# RS485_Xbus_Mini.net
KiCad netlist of a schematic drawn in Altium Designer
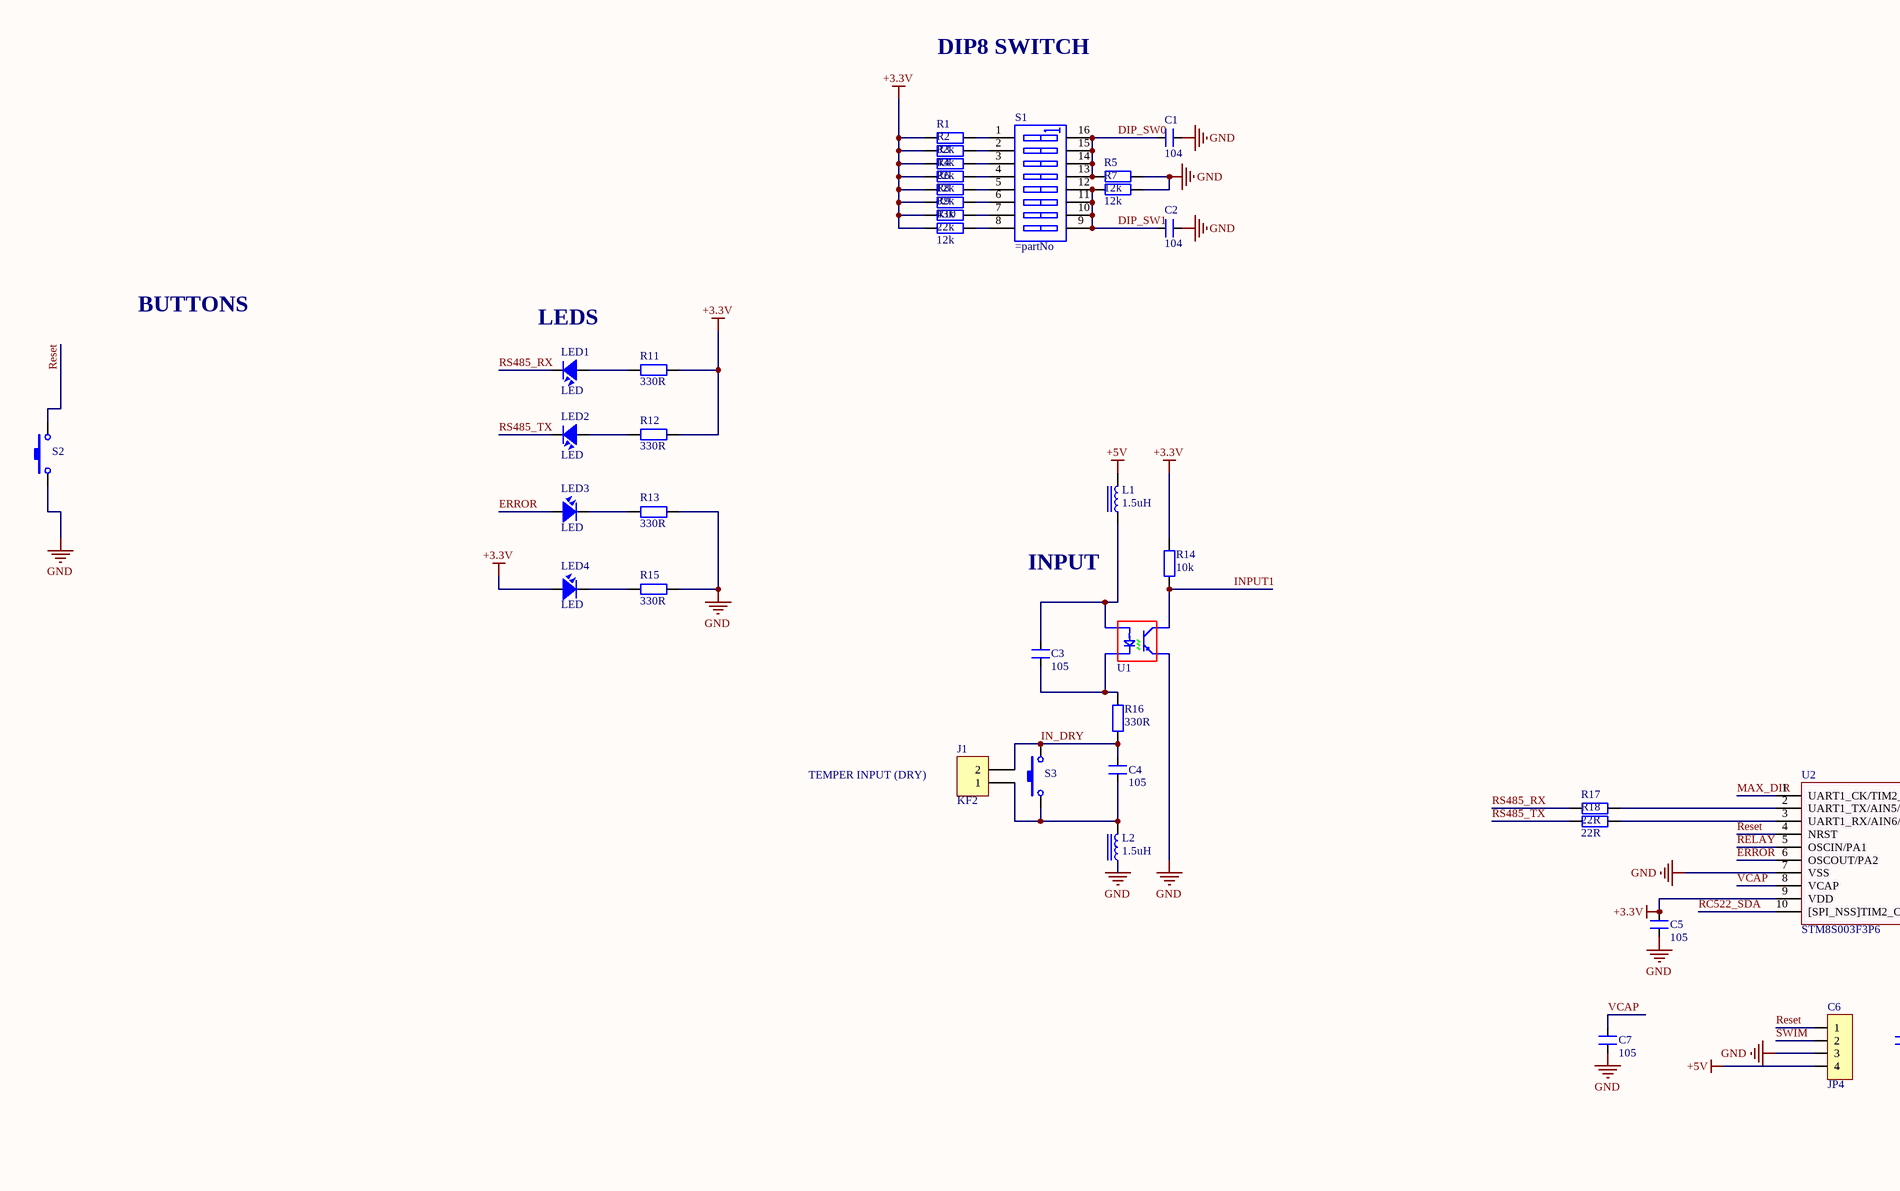
[diagram p0: RS485_Xbus_Mini.SchDoc, left]
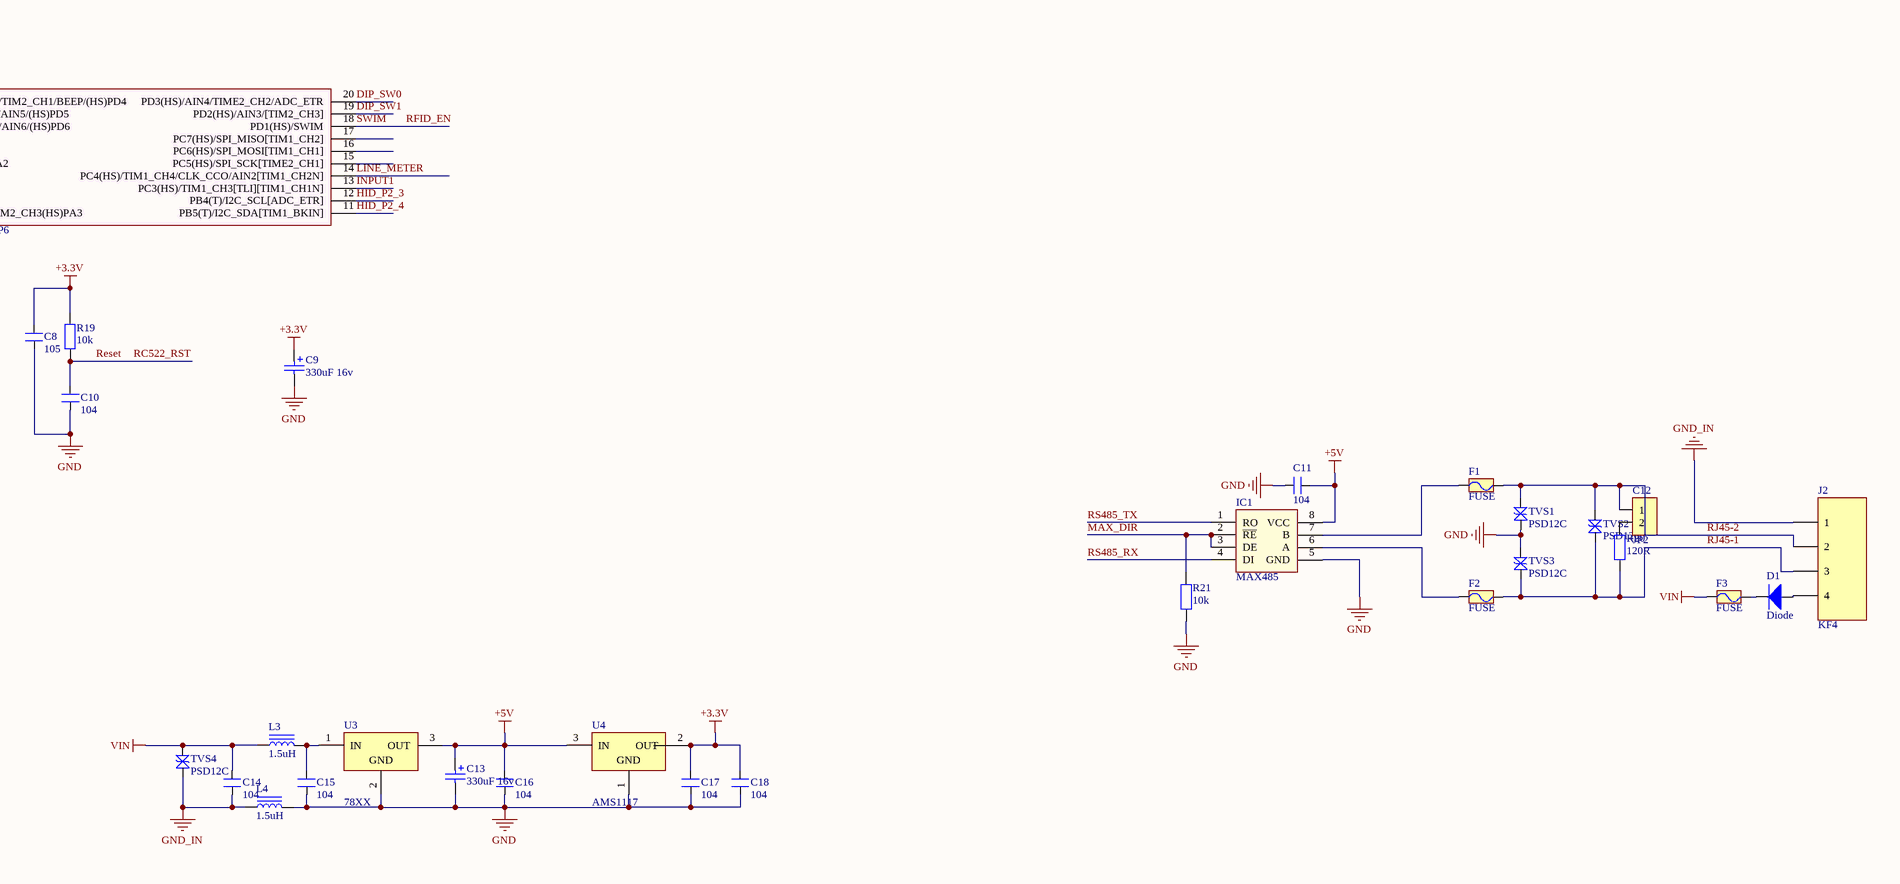
[diagram p1: RS485_Xbus_Mini.SchDoc, right]

(export (version "E")
  (design (tool "Eeschema 10.0.6"))
  (components
    (comp (ref "C1")
      (value "104")
      (footprint "SM-0805")
      (description "Cap SMD")
      (libsource (lib "OBIT_TESLA") (part "CM"))
    )
    (comp (ref "C2")
      (value "104")
      (footprint "SM-0805")
      (description "Cap SMD")
      (libsource (lib "OBIT_TESLA") (part "CM"))
    )
    (comp (ref "C3")
      (value "105")
      (footprint "SM-0805")
      (description "Cap SMD")
      (libsource (lib "OBIT_TESLA") (part "CM"))
    )
    (comp (ref "C4")
      (value "105")
      (footprint "SM-0805")
      (description "Cap SMD")
      (libsource (lib "OBIT_TESLA") (part "CM"))
    )
    (comp (ref "C5")
      (value "105")
      (footprint "SM-0805")
      (description "Cap SMD")
      (libsource (lib "OBIT_TESLA") (part "CM"))
    )
    (comp (ref "C6")
      (value "JP4")
      (footprint "JP4-C1T")
      (description "WR-PHD 2.54 mm Angled Socket Header")
      (fields
        (field (name "MANUFACTURER") "Würth Elektronik eiSos GmbH")
        (field (name "PARTNO") "613004143121")
        (field (name "CREATED BY") "Karrer Zheng")
      )
      (libsource (lib "OBIT_TESLA") (part "JP4"))
    )
    (comp (ref "C7")
      (value "105")
      (footprint "SM-0805")
      (description "Cap SMD")
      (libsource (lib "OBIT_TESLA") (part "CM"))
    )
    (comp (ref "C8")
      (value "105")
      (footprint "SM-0805")
      (description "Cap SMD")
      (libsource (lib "OBIT_TESLA") (part "CM"))
    )
    (comp (ref "C9")
      (value "330uF 16v")
      (footprint "WCAP-AS5H_8x10.5")
      (description "https://banlinhkien.vn/goods-2220-tu-nhom-330uf-16v-8x10mm.html")
      (fields (field (name "PARTNUMBER") "865230153006") (field (name "PUBLISHER") "Wurth Elektronik"))
      (libsource (lib "Library") (part "CAP/330uF/6.3V/865230153006"))
    )
    (comp (ref "C10")
      (value "104")
      (footprint "SM-0805")
      (description "Cap SMD")
      (libsource (lib "OBIT_TESLA") (part "CM"))
    )
    (comp (ref "C11")
      (value "104")
      (footprint "SM-0805")
      (description "Cap SMD")
      (libsource (lib "OBIT_TESLA") (part "CM"))
    )
    (comp (ref "C12")
      (value "JP2")
      (footprint "JP2-D1T")
      (description "WR-PHD 2.54 mm Angled Socket Header")
      (fields
        (field (name "MANUFACTURER") "Würth Elektronik eiSos GmbH")
        (field (name "PARTNO") "613002143121")
        (field (name "CREATED BY") "Karrer Zheng")
      )
      (libsource (lib "OBIT_TESLA") (part "JP2"))
    )
    (comp (ref "C13")
      (value "330uF 16v")
      (footprint "WCAP-AS5H_8x10.5")
      (description "https://banlinhkien.vn/goods-2220-tu-nhom-330uf-16v-8x10mm.html")
      (fields (field (name "PARTNUMBER") "865230153006") (field (name "PUBLISHER") "Wurth Elektronik"))
      (libsource (lib "Library") (part "CAP/330uF/6.3V/865230153006"))
    )
    (comp (ref "C14")
      (value "104")
      (footprint "SM-0805")
      (description "Cap SMD")
      (libsource (lib "OBIT_TESLA") (part "CM"))
    )
    (comp (ref "C15")
      (value "104")
      (footprint "SM-0805")
      (description "Cap SMD")
      (libsource (lib "OBIT_TESLA") (part "CM"))
    )
    (comp (ref "C16")
      (value "104")
      (footprint "SM-0805")
      (description "Cap SMD")
      (libsource (lib "OBIT_TESLA") (part "CM"))
    )
    (comp (ref "C17")
      (value "104")
      (footprint "SM-0805")
      (description "Cap SMD")
      (libsource (lib "OBIT_TESLA") (part "CM"))
    )
    (comp (ref "C18")
      (value "104")
      (footprint "SM-0805")
      (description "Cap SMD")
      (libsource (lib "OBIT_TESLA") (part "CM"))
    )
    (comp (ref "D1") (value "Diode") (footprint "DIO-SMD-106") (libsource (lib "OBIT_TESLA") (part "Diode")))
    (comp (ref "F1") (value "FUSE") (footprint "RES-SMD-1812") (libsource (lib "OBIT_TESLA") (part "FUSE")))
    (comp (ref "F2") (value "FUSE") (footprint "RES-SMD-1812") (libsource (lib "OBIT_TESLA") (part "FUSE")))
    (comp (ref "F3") (value "FUSE") (footprint "RES-SMD-1812") (libsource (lib "OBIT_TESLA") (part "FUSE")))
    (comp (ref "IC1")
      (value "MAX485")
      (footprint "SO-8")
      (description "RS232 - RS485 (Same sn75176)")
      (libsource (lib "syhaunguyen") (part "MAX485"))
    )
    (comp (ref "J1")
      (value "KF2")
      (footprint "KF2-5.08")
      (fields
        (field (name "MANUFACTURER") "Würth Elektronik eiSos GmbH")
        (field (name "PARTNO") "691103110002")
        (field (name "CREATED BY") "Karrer Zheng")
      )
      (libsource (lib "OBIT_TESLA") (part "KF2"))
    )
    (comp (ref "J2")
      (value "KF4")
      (footprint "KF4-5.08")
      (fields
        (field (name "MANUFACTURER") "Würth Elektronik eiSos GmbH")
        (field (name "PARTNO") "691133710004")
        (field (name "CREATED BY") "Baojun Chen")
      )
      (libsource (lib "OBIT_TESLA") (part "KF4"))
    )
    (comp (ref "L1")
      (value "1.5uH")
      (footprint "FER 0805/2012")
      (description "SMT Inductor")
      (libsource (lib "OBIT_TESLA") (part "Inductor"))
    )
    (comp (ref "L2")
      (value "1.5uH")
      (footprint "FER 0805/2012")
      (description "SMT Inductor")
      (libsource (lib "OBIT_TESLA") (part "Inductor"))
    )
    (comp (ref "L3")
      (value "1.5uH")
      (footprint "FER 0805/2012")
      (description "SMT Inductor")
      (libsource (lib "OBIT_TESLA") (part "Inductor"))
    )
    (comp (ref "L4")
      (value "1.5uH")
      (footprint "FER 0805/2012")
      (description "SMT Inductor")
      (libsource (lib "OBIT_TESLA") (part "Inductor"))
    )
    (comp (ref "LED1")
      (value "LED")
      (footprint "SM-LED-0805-Green")
      (libsource (lib "OBIT_TESLA") (part "LED"))
    )
    (comp (ref "LED2")
      (value "LED")
      (footprint "SM-LED-0805-Blue")
      (libsource (lib "OBIT_TESLA") (part "LED"))
    )
    (comp (ref "LED3")
      (value "LED")
      (footprint "SM-LED-0805-Red")
      (libsource (lib "OBIT_TESLA") (part "LED"))
    )
    (comp (ref "LED4")
      (value "LED")
      (footprint "SM-LED-0805-Red")
      (libsource (lib "OBIT_TESLA") (part "LED"))
    )
    (comp (ref "R1")
      (value "82k")
      (footprint "RES-SMD-0805")
      (description "Resistor R1/4W")
      (libsource (lib "OBIT_TESLA") (part "R"))
    )
    (comp (ref "R2")
      (value "43k")
      (footprint "RES-SMD-0805")
      (description "Resistor R1/4W")
      (libsource (lib "OBIT_TESLA") (part "R"))
    )
    (comp (ref "R3")
      (value "22k")
      (footprint "RES-SMD-0805")
      (description "Resistor R1/4W")
      (libsource (lib "OBIT_TESLA") (part "R"))
    )
    (comp (ref "R4")
      (value "12k")
      (footprint "RES-SMD-0805")
      (description "Resistor R1/4W")
      (libsource (lib "OBIT_TESLA") (part "R"))
    )
    (comp (ref "R5")
      (value "12k")
      (footprint "RES-SMD-0805")
      (description "Resistor R1/4W")
      (libsource (lib "OBIT_TESLA") (part "R"))
    )
    (comp (ref "R6")
      (value "82k")
      (footprint "RES-SMD-0805")
      (description "Resistor R1/4W")
      (libsource (lib "OBIT_TESLA") (part "R"))
    )
    (comp (ref "R7")
      (value "12k")
      (footprint "RES-SMD-0805")
      (description "Resistor R1/4W")
      (libsource (lib "OBIT_TESLA") (part "R"))
    )
    (comp (ref "R8")
      (value "43k")
      (footprint "RES-SMD-0805")
      (description "Resistor R1/4W")
      (libsource (lib "OBIT_TESLA") (part "R"))
    )
    (comp (ref "R9")
      (value "22k")
      (footprint "RES-SMD-0805")
      (description "Resistor R1/4W")
      (libsource (lib "OBIT_TESLA") (part "R"))
    )
    (comp (ref "R10")
      (value "12k")
      (footprint "RES-SMD-0805")
      (description "Resistor R1/4W")
      (libsource (lib "OBIT_TESLA") (part "R"))
    )
    (comp (ref "R11")
      (value "330R")
      (footprint "RES-SMD-0805")
      (description "Resistor R1/4W")
      (libsource (lib "OBIT_TESLA") (part "R"))
    )
    (comp (ref "R12")
      (value "330R")
      (footprint "RES-SMD-0805")
      (description "Resistor R1/4W")
      (libsource (lib "OBIT_TESLA") (part "R"))
    )
    (comp (ref "R13")
      (value "330R")
      (footprint "RES-SMD-0805")
      (description "Resistor R1/4W")
      (libsource (lib "OBIT_TESLA") (part "R"))
    )
    (comp (ref "R14")
      (value "10k")
      (footprint "RES-SMD-0805")
      (description "Resistor R1/4W")
      (libsource (lib "OBIT_TESLA") (part "R"))
    )
    (comp (ref "R15")
      (value "330R")
      (footprint "RES-SMD-0805")
      (description "Resistor R1/4W")
      (libsource (lib "OBIT_TESLA") (part "R"))
    )
    (comp (ref "R16")
      (value "330R")
      (footprint "RES-SMD-0805")
      (description "Resistor R1/4W")
      (libsource (lib "OBIT_TESLA") (part "R"))
    )
    (comp (ref "R17")
      (value "22R")
      (footprint "RES-SMD-0805")
      (description "Resistor R1/4W")
      (libsource (lib "OBIT_TESLA") (part "R"))
    )
    (comp (ref "R18")
      (value "22R")
      (footprint "RES-SMD-0805")
      (description "Resistor R1/4W")
      (libsource (lib "OBIT_TESLA") (part "R"))
    )
    (comp (ref "R19")
      (value "10k")
      (footprint "RES-SMD-0805")
      (description "Resistor R1/4W")
      (libsource (lib "OBIT_TESLA") (part "R"))
    )
    (comp (ref "R20")
      (value "120R")
      (footprint "RES-SMD-0805")
      (description "Resistor R1/4W")
      (libsource (lib "OBIT_TESLA") (part "R"))
    )
    (comp (ref "R21")
      (value "10k")
      (footprint "RES-SMD-0805")
      (description "Resistor R1/4W")
      (libsource (lib "OBIT_TESLA") (part "R"))
    )
    (comp (ref "S1")
      (value "~")
      (footprint "SW-DIP8")
      (description "WS-DITV 2.54 mm small compact THT flat actuator with top tape")
      (fields
        (field (name "MANUFACTURER") "Wurth Elektronik")
        (field (name "PART NO.") "418127160908")
        (field (name "CREATED BY") "Baojun Chen")
      )
      (libsource (lib "OBIT_TESLA") (part "SWDIP8"))
    )
    (comp (ref "S2")
      (value "SW")
      (footprint "BUTTON-SMD 2PIN")
      (description "Switch-Button")
      (fields (field (name "PUBLISHER") "Altium Limited"))
      (libsource (lib "OBIT_TESLA") (part "SW-Button"))
    )
    (comp (ref "S3")
      (value "SW")
      (footprint "BUTTON-SMD 2PIN")
      (description "Switch-Button")
      (fields (field (name "PUBLISHER") "Altium Limited"))
      (libsource (lib "OBIT_TESLA") (part "SW-Button"))
    )
    (comp (ref "TVS1")
      (value "PSD12C")
      (footprint "DIO-SMD-123")
      (libsource (lib "OBIT_TESLA") (part "Diode TVS"))
    )
    (comp (ref "TVS2")
      (value "PSD12C")
      (footprint "DIO-SMD-123")
      (libsource (lib "OBIT_TESLA") (part "Diode TVS"))
    )
    (comp (ref "TVS3")
      (value "PSD12C")
      (footprint "DIO-SMD-123")
      (libsource (lib "OBIT_TESLA") (part "Diode TVS"))
    )
    (comp (ref "TVS4")
      (value "PSD12C")
      (footprint "DIO-SMD-B")
      (libsource (lib "OBIT_TESLA") (part "Diode TVS"))
    )
    (comp (ref "U1")
      (value "EL3H7 Opto")
      (footprint "SSOP4")
      (libsource (lib "OBIT_TESLA") (part "EL3H7 Opto"))
    )
    (comp (ref "U2")
      (value "STM8S003F3P6")
      (footprint "TSOP20")
      (description "MCU 8BIT 8KB FLASH TSSOP20")
      (libsource (lib "MCU") (part "STM8S003F3P6"))
    )
    (comp (ref "U3") (value "78XX") (footprint "SOT-89-321") (libsource (lib "OBIT_TESLA") (part "LM78XX")))
    (comp (ref "U4") (value "AMS1117") (footprint "SOT223") (libsource (lib "OBIT_TESLA") (part "AMS117")))
  )
  (nets
    (net (code "1") (name "+3.3V") (class "Default")
      (node (ref "C17") (pin "2") (pinfunction "2_2") (pintype "passive"))
      (node (ref "C18") (pin "2") (pinfunction "2_2") (pintype "passive"))
      (node (ref "C5") (pin "2") (pinfunction "2_2") (pintype "passive"))
      (node (ref "C8") (pin "2") (pinfunction "2_2") (pintype "passive"))
      (node (ref "C9") (pin "1") (pinfunction "P_1") (pintype "passive"))
      (node (ref "LED4") (pin "1") (pinfunction "1_1") (pintype "passive"))
      (node (ref "R1") (pin "2") (pinfunction "2_2") (pintype "passive"))
      (node (ref "R10") (pin "2") (pinfunction "2_2") (pintype "passive"))
      (node (ref "R11") (pin "1") (pinfunction "1_1") (pintype "passive"))
      (node (ref "R12") (pin "1") (pinfunction "1_1") (pintype "passive"))
      (node (ref "R14") (pin "2") (pinfunction "2_2") (pintype "passive"))
      (node (ref "R19") (pin "2") (pinfunction "2_2") (pintype "passive"))
      (node (ref "R2") (pin "2") (pinfunction "2_2") (pintype "passive"))
      (node (ref "R3") (pin "2") (pinfunction "2_2") (pintype "passive"))
      (node (ref "R4") (pin "2") (pinfunction "2_2") (pintype "passive"))
      (node (ref "R6") (pin "2") (pinfunction "2_2") (pintype "passive"))
      (node (ref "R8") (pin "2") (pinfunction "2_2") (pintype "passive"))
      (node (ref "R9") (pin "2") (pinfunction "2_2") (pintype "passive"))
      (node (ref "U2") (pin "9") (pinfunction "VDD_9") (pintype "passive"))
      (node (ref "U4") (pin "2") (pinfunction "OUT_2") (pintype "power_in"))
      (node (ref "U4") (pin "4") (pinfunction "4_4") (pintype "passive"))
    )
    (net (code "2") (name "+5V") (class "Default")
      (node (ref "C11") (pin "1") (pinfunction "1_1") (pintype "passive"))
      (node (ref "C13") (pin "1") (pinfunction "P_1") (pintype "passive"))
      (node (ref "C16") (pin "2") (pinfunction "2_2") (pintype "passive"))
      (node (ref "C6") (pin "4") (pinfunction "4_4") (pintype "passive"))
      (node (ref "IC1") (pin "8") (pinfunction "VCC_8") (pintype "passive"))
      (node (ref "L1") (pin "2") (pinfunction "2_2") (pintype "passive"))
      (node (ref "U3") (pin "3") (pinfunction "OUT_3") (pintype "power_in"))
      (node (ref "U4") (pin "3") (pinfunction "IN_3") (pintype "power_in"))
    )
    (net (code "3") (name "/DIP_SW0") (class "Default")
      (node (ref "C1") (pin "2") (pinfunction "2_2") (pintype "passive"))
      (node (ref "R5") (pin "2") (pinfunction "2_2") (pintype "passive"))
      (node (ref "S1") (pin "13") (pinfunction "13_13") (pintype "passive"))
      (node (ref "S1") (pin "14") (pinfunction "14_14") (pintype "passive"))
      (node (ref "S1") (pin "15") (pinfunction "15_15") (pintype "passive"))
      (node (ref "S1") (pin "16") (pinfunction "16_16") (pintype "passive"))
      (node (ref "U2") (pin "20") (pinfunction "PD3(HS)/AIN4/TIME2_CH2/ADC_ETR_20") (pintype "passive"))
    )
    (net (code "4") (name "/DIP_SW1") (class "Default")
      (node (ref "C2") (pin "2") (pinfunction "2_2") (pintype "passive"))
      (node (ref "R7") (pin "2") (pinfunction "2_2") (pintype "passive"))
      (node (ref "S1") (pin "10") (pinfunction "10_10") (pintype "passive"))
      (node (ref "S1") (pin "11") (pinfunction "11_11") (pintype "passive"))
      (node (ref "S1") (pin "12") (pinfunction "12_12") (pintype "passive"))
      (node (ref "S1") (pin "9") (pinfunction "9_9") (pintype "passive"))
      (node (ref "U2") (pin "19") (pinfunction "PD2(HS)/AIN3/[TIM2_CH3]_19") (pintype "passive"))
    )
    (net (code "5") (name "/ERROR") (class "Default")
      (node (ref "LED3") (pin "1") (pinfunction "1_1") (pintype "passive"))
      (node (ref "U2") (pin "6") (pinfunction "OSCOUT/PA2_6") (pintype "passive"))
    )
    (net (code "6") (name "/HID_P2_3") (class "Default")
      (node (ref "U2") (pin "12") (pinfunction "PB4(T)/I2C_SCL[ADC_ETR]_12") (pintype "passive"))
    )
    (net (code "7") (name "/HID_P2_4") (class "Default")
      (node (ref "U2") (pin "11") (pinfunction "PB5(T)/I2C_SDA[TIM1_BKIN]_11") (pintype "passive"))
    )
    (net (code "8") (name "/INPUT1") (class "Default")
      (node (ref "R14") (pin "1") (pinfunction "1_1") (pintype "passive"))
      (node (ref "U1") (pin "4") (pinfunction "4_4") (pintype "passive"))
      (node (ref "U2") (pin "13") (pinfunction "PC3(HS)/TIM1_CH3[TLI][TIM1_CH1N]_13") (pintype "passive"))
    )
    (net (code "9") (name "/IN_DRY") (class "Default")
      (node (ref "C4") (pin "2") (pinfunction "2_2") (pintype "passive"))
      (node (ref "J1") (pin "2") (pinfunction "2_2") (pintype "passive"))
      (node (ref "R16") (pin "1") (pinfunction "1_1") (pintype "passive"))
      (node (ref "S3") (pin "2") (pinfunction "2_2") (pintype "passive"))
    )
    (net (code "10") (name "/LINE_METER") (class "Default")
      (node (ref "U2") (pin "14") (pinfunction "PC4(HS)/TIM1_CH4/CLK_CCO/AIN2[TIM1_CH2N]_14") (pintype "passive"))
    )
    (net (code "11") (name "/MAX_DIR") (class "Default")
      (node (ref "IC1") (pin "2") (pinfunction "~{RE}_2") (pintype "passive"))
      (node (ref "IC1") (pin "3") (pinfunction "DE_3") (pintype "passive"))
      (node (ref "R21") (pin "1") (pinfunction "1_1") (pintype "passive"))
      (node (ref "U2") (pin "1") (pinfunction "UART1_CK/TIM2_CH1/BEEP/(HS)PD4_1") (pintype "passive"))
    )
    (net (code "12") (name "/RC522_RST") (class "Default")
      (node (ref "C10") (pin "2") (pinfunction "2_2") (pintype "passive"))
      (node (ref "C6") (pin "1") (pinfunction "1_1") (pintype "passive"))
      (node (ref "R19") (pin "1") (pinfunction "1_1") (pintype "passive"))
      (node (ref "S2") (pin "2") (pinfunction "2_2") (pintype "passive"))
      (node (ref "U2") (pin "4") (pinfunction "NRST_4") (pintype "passive"))
    )
    (net (code "13") (name "/RC522_SDA") (class "Default")
      (node (ref "U2") (pin "10") (pinfunction "[SPI_NSS]TIM2_CH3(HS)PA3_10") (pintype "passive"))
    )
    (net (code "14") (name "/RELAY") (class "Default")
      (node (ref "U2") (pin "5") (pinfunction "OSCIN/PA1_5") (pintype "passive"))
    )
    (net (code "15") (name "/RFID_EN") (class "Default")
      (node (ref "C6") (pin "2") (pinfunction "2_2") (pintype "passive"))
      (node (ref "U2") (pin "18") (pinfunction "PD1(HS)/SWIM_18") (pintype "passive"))
    )
    (net (code "16") (name "/RJ45-1") (class "Default")
      (node (ref "F2") (pin "2") (pinfunction "2_2") (pintype "passive"))
      (node (ref "J2") (pin "3") (pinfunction "3_3") (pintype "passive"))
      (node (ref "R20") (pin "2") (pinfunction "2_2") (pintype "passive"))
      (node (ref "TVS2") (pin "1") (pinfunction "1_1") (pintype "passive"))
      (node (ref "TVS3") (pin "1") (pinfunction "1_1") (pintype "passive"))
    )
    (net (code "17") (name "/RJ45-2") (class "Default")
      (node (ref "C12") (pin "1") (pinfunction "1_1") (pintype "passive"))
      (node (ref "F1") (pin "2") (pinfunction "2_2") (pintype "passive"))
      (node (ref "J2") (pin "2") (pinfunction "2_2") (pintype "passive"))
      (node (ref "TVS1") (pin "2") (pinfunction "2_2") (pintype "passive"))
      (node (ref "TVS2") (pin "2") (pinfunction "2_2") (pintype "passive"))
    )
    (net (code "18") (name "/RS485_RX") (class "Default")
      (node (ref "IC1") (pin "4") (pinfunction "DI_4") (pintype "passive"))
      (node (ref "LED1") (pin "2") (pinfunction "2_2") (pintype "passive"))
      (node (ref "R17") (pin "2") (pinfunction "2_2") (pintype "passive"))
    )
    (net (code "19") (name "/RS485_TX") (class "Default")
      (node (ref "IC1") (pin "1") (pinfunction "RO_1") (pintype "passive"))
      (node (ref "LED2") (pin "2") (pinfunction "2_2") (pintype "passive"))
      (node (ref "R18") (pin "2") (pinfunction "2_2") (pintype "passive"))
    )
    (net (code "20") (name "/VCAP") (class "Default")
      (node (ref "C7") (pin "2") (pinfunction "2_2") (pintype "passive"))
      (node (ref "U2") (pin "8") (pinfunction "VCAP_8") (pintype "passive"))
    )
    (net (code "21") (name "GND") (class "Default")
      (node (ref "C1") (pin "1") (pinfunction "1_1") (pintype "passive"))
      (node (ref "C10") (pin "1") (pinfunction "1_1") (pintype "passive"))
      (node (ref "C11") (pin "2") (pinfunction "2_2") (pintype "passive"))
      (node (ref "C13") (pin "2") (pinfunction "N_2") (pintype "passive"))
      (node (ref "C15") (pin "1") (pinfunction "1_1") (pintype "passive"))
      (node (ref "C16") (pin "1") (pinfunction "1_1") (pintype "passive"))
      (node (ref "C17") (pin "1") (pinfunction "1_1") (pintype "passive"))
      (node (ref "C18") (pin "1") (pinfunction "1_1") (pintype "passive"))
      (node (ref "C2") (pin "1") (pinfunction "1_1") (pintype "passive"))
      (node (ref "C5") (pin "1") (pinfunction "1_1") (pintype "passive"))
      (node (ref "C6") (pin "3") (pinfunction "3_3") (pintype "passive"))
      (node (ref "C7") (pin "1") (pinfunction "1_1") (pintype "passive"))
      (node (ref "C8") (pin "1") (pinfunction "1_1") (pintype "passive"))
      (node (ref "C9") (pin "2") (pinfunction "N_2") (pintype "passive"))
      (node (ref "IC1") (pin "5") (pinfunction "GND_5") (pintype "passive"))
      (node (ref "L2") (pin "1") (pinfunction "1_1") (pintype "passive"))
      (node (ref "L4") (pin "2") (pinfunction "2_2") (pintype "passive"))
      (node (ref "R13") (pin "1") (pinfunction "1_1") (pintype "passive"))
      (node (ref "R15") (pin "1") (pinfunction "1_1") (pintype "passive"))
      (node (ref "R21") (pin "2") (pinfunction "2_2") (pintype "passive"))
      (node (ref "R5") (pin "1") (pinfunction "1_1") (pintype "passive"))
      (node (ref "R7") (pin "1") (pinfunction "1_1") (pintype "passive"))
      (node (ref "S2") (pin "1") (pinfunction "1_1") (pintype "passive"))
      (node (ref "TVS1") (pin "1") (pinfunction "1_1") (pintype "passive"))
      (node (ref "TVS3") (pin "2") (pinfunction "2_2") (pintype "passive"))
      (node (ref "U1") (pin "3") (pinfunction "3_3") (pintype "passive"))
      (node (ref "U2") (pin "7") (pinfunction "VSS_7") (pintype "passive"))
      (node (ref "U3") (pin "2") (pinfunction "GND_2") (pintype "power_in"))
      (node (ref "U4") (pin "1") (pinfunction "GND_1") (pintype "power_in"))
    )
    (net (code "22") (name "GND_IN") (class "Default")
      (node (ref "C14") (pin "1") (pinfunction "1_1") (pintype "passive"))
      (node (ref "J2") (pin "1") (pinfunction "1_1") (pintype "passive"))
      (node (ref "L4") (pin "1") (pinfunction "1_1") (pintype "passive"))
      (node (ref "TVS4") (pin "1") (pinfunction "1_1") (pintype "passive"))
    )
    (net (code "23") (name "Net-(C3-Pad1)") (class "Default")
      (node (ref "C3") (pin "1") (pinfunction "1_1") (pintype "passive"))
      (node (ref "R16") (pin "2") (pinfunction "2_2") (pintype "passive"))
      (node (ref "U1") (pin "2") (pinfunction "2_2") (pintype "passive"))
    )
    (net (code "24") (name "Net-(C3-Pad2)") (class "Default")
      (node (ref "C3") (pin "2") (pinfunction "2_2") (pintype "passive"))
      (node (ref "L1") (pin "1") (pinfunction "1_1") (pintype "passive"))
      (node (ref "U1") (pin "1") (pinfunction "1_1") (pintype "passive"))
    )
    (net (code "25") (name "Net-(C4-Pad1)") (class "Default")
      (node (ref "C4") (pin "1") (pinfunction "1_1") (pintype "passive"))
      (node (ref "J1") (pin "1") (pinfunction "1_1") (pintype "passive"))
      (node (ref "L2") (pin "2") (pinfunction "2_2") (pintype "passive"))
      (node (ref "S3") (pin "1") (pinfunction "1_1") (pintype "passive"))
    )
    (net (code "26") (name "Net-(C12-Pad2)") (class "Default")
      (node (ref "C12") (pin "2") (pinfunction "2_2") (pintype "passive"))
      (node (ref "R20") (pin "1") (pinfunction "1_1") (pintype "passive"))
    )
    (net (code "27") (name "Net-(D1-Pad1)") (class "Default")
      (node (ref "D1") (pin "1") (pinfunction "1_1") (pintype "passive"))
      (node (ref "J2") (pin "4") (pinfunction "4_4") (pintype "passive"))
    )
    (net (code "28") (name "Net-(D1-Pad2)") (class "Default")
      (node (ref "D1") (pin "2") (pinfunction "2_2") (pintype "passive"))
      (node (ref "F3") (pin "2") (pinfunction "2_2") (pintype "passive"))
    )
    (net (code "29") (name "Net-(IC1-A)") (class "Default")
      (node (ref "F2") (pin "1") (pinfunction "1_1") (pintype "passive"))
      (node (ref "IC1") (pin "6") (pinfunction "A_6") (pintype "passive"))
    )
    (net (code "30") (name "Net-(IC1-B)") (class "Default")
      (node (ref "F1") (pin "1") (pinfunction "1_1") (pintype "passive"))
      (node (ref "IC1") (pin "7") (pinfunction "B_7") (pintype "passive"))
    )
    (net (code "31") (name "Net-(LED1-Pad1)") (class "Default")
      (node (ref "LED1") (pin "1") (pinfunction "1_1") (pintype "passive"))
      (node (ref "R11") (pin "2") (pinfunction "2_2") (pintype "passive"))
    )
    (net (code "32") (name "Net-(LED2-Pad1)") (class "Default")
      (node (ref "LED2") (pin "1") (pinfunction "1_1") (pintype "passive"))
      (node (ref "R12") (pin "2") (pinfunction "2_2") (pintype "passive"))
    )
    (net (code "33") (name "Net-(LED3-Pad2)") (class "Default")
      (node (ref "LED3") (pin "2") (pinfunction "2_2") (pintype "passive"))
      (node (ref "R13") (pin "2") (pinfunction "2_2") (pintype "passive"))
    )
    (net (code "34") (name "Net-(LED4-Pad2)") (class "Default")
      (node (ref "LED4") (pin "2") (pinfunction "2_2") (pintype "passive"))
      (node (ref "R15") (pin "2") (pinfunction "2_2") (pintype "passive"))
    )
    (net (code "35") (name "Net-(R1-Pad1)") (class "Default")
      (node (ref "R1") (pin "1") (pinfunction "1_1") (pintype "passive"))
      (node (ref "S1") (pin "1") (pinfunction "1_1") (pintype "passive"))
    )
    (net (code "36") (name "Net-(R2-Pad1)") (class "Default")
      (node (ref "R2") (pin "1") (pinfunction "1_1") (pintype "passive"))
      (node (ref "S1") (pin "2") (pinfunction "2_2") (pintype "passive"))
    )
    (net (code "37") (name "Net-(R3-Pad1)") (class "Default")
      (node (ref "R3") (pin "1") (pinfunction "1_1") (pintype "passive"))
      (node (ref "S1") (pin "3") (pinfunction "3_3") (pintype "passive"))
    )
    (net (code "38") (name "Net-(R4-Pad1)") (class "Default")
      (node (ref "R4") (pin "1") (pinfunction "1_1") (pintype "passive"))
      (node (ref "S1") (pin "4") (pinfunction "4_4") (pintype "passive"))
    )
    (net (code "39") (name "Net-(R6-Pad1)") (class "Default")
      (node (ref "R6") (pin "1") (pinfunction "1_1") (pintype "passive"))
      (node (ref "S1") (pin "5") (pinfunction "5_5") (pintype "passive"))
    )
    (net (code "40") (name "Net-(R8-Pad1)") (class "Default")
      (node (ref "R8") (pin "1") (pinfunction "1_1") (pintype "passive"))
      (node (ref "S1") (pin "6") (pinfunction "6_6") (pintype "passive"))
    )
    (net (code "41") (name "Net-(R9-Pad1)") (class "Default")
      (node (ref "R9") (pin "1") (pinfunction "1_1") (pintype "passive"))
      (node (ref "S1") (pin "7") (pinfunction "7_7") (pintype "passive"))
    )
    (net (code "42") (name "Net-(R10-Pad1)") (class "Default")
      (node (ref "R10") (pin "1") (pinfunction "1_1") (pintype "passive"))
      (node (ref "S1") (pin "8") (pinfunction "8_8") (pintype "passive"))
    )
    (net (code "43") (name "Net-(U2-UART1_RX{slash}AIN6{slash}(HS)PD6)") (class "Default")
      (node (ref "R18") (pin "1") (pinfunction "1_1") (pintype "passive"))
      (node (ref "U2") (pin "3") (pinfunction "UART1_RX/AIN6/(HS)PD6_3") (pintype "passive"))
    )
    (net (code "44") (name "Net-(U2-UART1_TX{slash}AIN5{slash}(HS)PD5)") (class "Default")
      (node (ref "R17") (pin "1") (pinfunction "1_1") (pintype "passive"))
      (node (ref "U2") (pin "2") (pinfunction "UART1_TX/AIN5/(HS)PD5_2") (pintype "passive"))
    )
    (net (code "45") (name "Net-(U3-IN)") (class "Default")
      (node (ref "C15") (pin "2") (pinfunction "2_2") (pintype "passive"))
      (node (ref "L3") (pin "2") (pinfunction "2_2") (pintype "passive"))
      (node (ref "U3") (pin "1") (pinfunction "IN_1") (pintype "power_in"))
    )
    (net (code "46") (name "VIN") (class "Default")
      (node (ref "C14") (pin "2") (pinfunction "2_2") (pintype "passive"))
      (node (ref "F3") (pin "1") (pinfunction "1_1") (pintype "passive"))
      (node (ref "L3") (pin "1") (pinfunction "1_1") (pintype "passive"))
      (node (ref "TVS4") (pin "2") (pinfunction "2_2") (pintype "passive"))
    )
    (net (code "47") (name "unconnected-(U2-PC5(HS){slash}SPI_SCK[TIME2_CH1]-Pad15)") (class "Default")
      (node (ref "U2") (pin "15") (pinfunction "PC5(HS)/SPI_SCK[TIME2_CH1]_15") (pintype "passive"))
    )
    (net (code "48") (name "unconnected-(U2-PC6(HS){slash}SPI_MOSI[TIM1_CH1]-Pad16)") (class "Default")
      (node (ref "U2") (pin "16") (pinfunction "PC6(HS)/SPI_MOSI[TIM1_CH1]_16") (pintype "passive"))
    )
    (net (code "49") (name "unconnected-(U2-PC7(HS){slash}SPI_MISO[TIM1_CH2]-Pad17)") (class "Default")
      (node (ref "U2") (pin "17") (pinfunction "PC7(HS)/SPI_MISO[TIM1_CH2]_17") (pintype "passive"))
    )
  )
)
